# debouncer.net
KiCad netlist of a schematic drawn in EAGLE
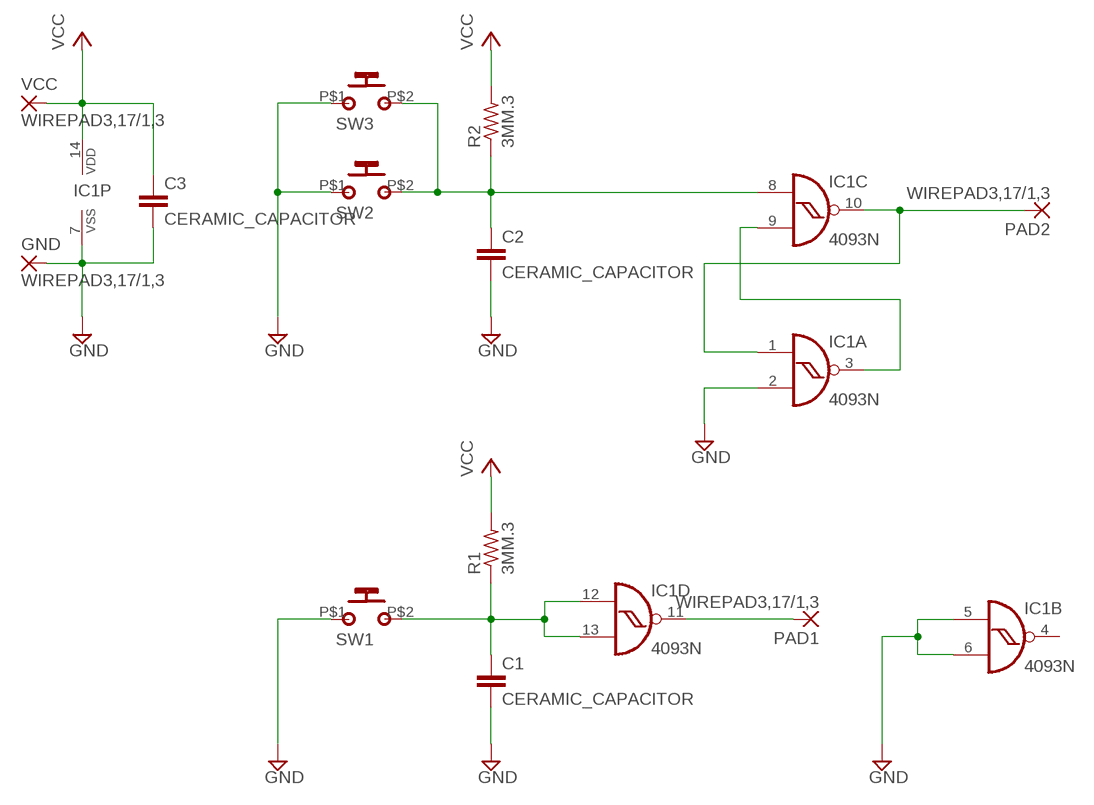
[diagram p0: schematic, sheet 1]

(export (version "E")
  (design (tool "Eeschema 10.0.6"))
  (components
    (comp (ref "C1")
      (value "CERAMIC_CAPACITOR")
      (footprint "eagle-import:CERAMIC_CAP")
      (libsource (lib "eagle-import") (part "CERAMIC_CAPACITOR"))
    )
    (comp (ref "C2")
      (value "CERAMIC_CAPACITOR")
      (footprint "eagle-import:CERAMIC_CAP")
      (libsource (lib "eagle-import") (part "CERAMIC_CAPACITOR"))
    )
    (comp (ref "C3")
      (value "CERAMIC_CAPACITOR")
      (footprint "eagle-import:CERAMIC_CAP")
      (libsource (lib "eagle-import") (part "CERAMIC_CAPACITOR"))
    )
    (comp (ref "GND")
      (value "WIREPAD3,17/1,3")
      (footprint "eagle-import:3,17_1,3")
      (libsource (lib "eagle-import") (part "WIREPAD3,17/1,3"))
    )
    (comp (ref "IC1")
      (value "4093N")
      (footprint "eagle-import:DIL14")
      (libsource (lib "eagle-import") (part "4093N"))
    )
    (comp (ref "PAD1")
      (value "WIREPAD3,17/1,3")
      (footprint "eagle-import:3,17_1,3")
      (libsource (lib "eagle-import") (part "WIREPAD3,17/1,3"))
    )
    (comp (ref "PAD2")
      (value "WIREPAD3,17/1,3")
      (footprint "eagle-import:3,17_1,3")
      (libsource (lib "eagle-import") (part "WIREPAD3,17/1,3"))
    )
    (comp (ref "R1")
      (value "3MM.3")
      (footprint "eagle-import:R0204_3")
      (libsource (lib "eagle-import") (part "3MM.3"))
    )
    (comp (ref "R2")
      (value "3MM.3")
      (footprint "eagle-import:R0204_3")
      (libsource (lib "eagle-import") (part "3MM.3"))
    )
    (comp (ref "SW1")
      (value "MOMENTARY_SW_SMALL")
      (footprint "eagle-import:MOMENTARY_SW_SMALL")
      (libsource (lib "eagle-import") (part "MOMENTARY_SW_SMALL"))
    )
    (comp (ref "SW2")
      (value "MOMENTARY_SW_SMALL")
      (footprint "eagle-import:MOMENTARY_SW_SMALL")
      (libsource (lib "eagle-import") (part "MOMENTARY_SW_SMALL"))
    )
    (comp (ref "SW3")
      (value "MOMENTARY_SW_SMALL")
      (footprint "eagle-import:MOMENTARY_SW_SMALL")
      (libsource (lib "eagle-import") (part "MOMENTARY_SW_SMALL"))
    )
    (comp (ref "VCC")
      (value "WIREPAD3,17/1,3")
      (footprint "eagle-import:3,17_1,3")
      (libsource (lib "eagle-import") (part "WIREPAD3,17/1,3"))
    )
  )
  (nets
    (net (code "1") (name "GND") (class "Default")
      (node (ref "C1") (pin "2") (pinfunction "2_2") (pintype "passive"))
      (node (ref "C2") (pin "2") (pinfunction "2_2") (pintype "passive"))
      (node (ref "C3") (pin "2") (pinfunction "2_2") (pintype "passive"))
      (node (ref "GND") (pin "1") (pinfunction "P_1") (pintype "passive"))
      (node (ref "IC1") (pin "2") (pinfunction "I1_2") (pintype "input"))
      (node (ref "IC1") (pin "5") (pinfunction "I0_5") (pintype "input"))
      (node (ref "IC1") (pin "6") (pinfunction "I1_6") (pintype "input"))
      (node (ref "IC1") (pin "7") (pinfunction "VSS_7") (pintype "power_in"))
      (node (ref "SW1") (pin "P$1") (pinfunction "P_P$1") (pintype "passive"))
      (node (ref "SW2") (pin "P$1") (pinfunction "P_P$1") (pintype "passive"))
      (node (ref "SW3") (pin "P$1") (pinfunction "P_P$1") (pintype "passive"))
    )
    (net (code "2") (name "Net-(IC1A-I0)") (class "Default")
      (node (ref "IC1") (pin "1") (pinfunction "I0_1") (pintype "input"))
      (node (ref "IC1") (pin "10") (pinfunction "O_10") (pintype "output"))
      (node (ref "PAD2") (pin "1") (pinfunction "P_1") (pintype "passive"))
    )
    (net (code "3") (name "Net-(IC1A-O)") (class "Default")
      (node (ref "IC1") (pin "3") (pinfunction "O_3") (pintype "output"))
      (node (ref "IC1") (pin "9") (pinfunction "I1_9") (pintype "input"))
    )
    (net (code "4") (name "Net-(IC1C-I0)") (class "Default")
      (node (ref "C2") (pin "1") (pinfunction "1_1") (pintype "passive"))
      (node (ref "IC1") (pin "8") (pinfunction "I0_8") (pintype "input"))
      (node (ref "R2") (pin "1") (pinfunction "1_1") (pintype "passive"))
      (node (ref "SW2") (pin "P$2") (pinfunction "S_P$2") (pintype "passive"))
      (node (ref "SW3") (pin "P$2") (pinfunction "S_P$2") (pintype "passive"))
    )
    (net (code "5") (name "Net-(IC1D-I0)") (class "Default")
      (node (ref "C1") (pin "1") (pinfunction "1_1") (pintype "passive"))
      (node (ref "IC1") (pin "12") (pinfunction "I0_12") (pintype "input"))
      (node (ref "IC1") (pin "13") (pinfunction "I1_13") (pintype "input"))
      (node (ref "R1") (pin "1") (pinfunction "1_1") (pintype "passive"))
      (node (ref "SW1") (pin "P$2") (pinfunction "S_P$2") (pintype "passive"))
    )
    (net (code "6") (name "Net-(IC1D-O)") (class "Default")
      (node (ref "IC1") (pin "11") (pinfunction "O_11") (pintype "output"))
      (node (ref "PAD1") (pin "1") (pinfunction "P_1") (pintype "passive"))
    )
    (net (code "7") (name "VCC") (class "Default")
      (node (ref "C3") (pin "1") (pinfunction "1_1") (pintype "passive"))
      (node (ref "IC1") (pin "14") (pinfunction "VDD_14") (pintype "power_in"))
      (node (ref "R1") (pin "2") (pinfunction "2_2") (pintype "passive"))
      (node (ref "R2") (pin "2") (pinfunction "2_2") (pintype "passive"))
      (node (ref "VCC") (pin "1") (pinfunction "P_1") (pintype "passive"))
    )
    (net (code "8") (name "unconnected-(IC1B-O-Pad4)") (class "Default")
      (node (ref "IC1") (pin "4") (pinfunction "O_4") (pintype "output"))
    )
  )
)
